# MultiGenPI.net
KiCad netlist of a schematic drawn in Altium Designer
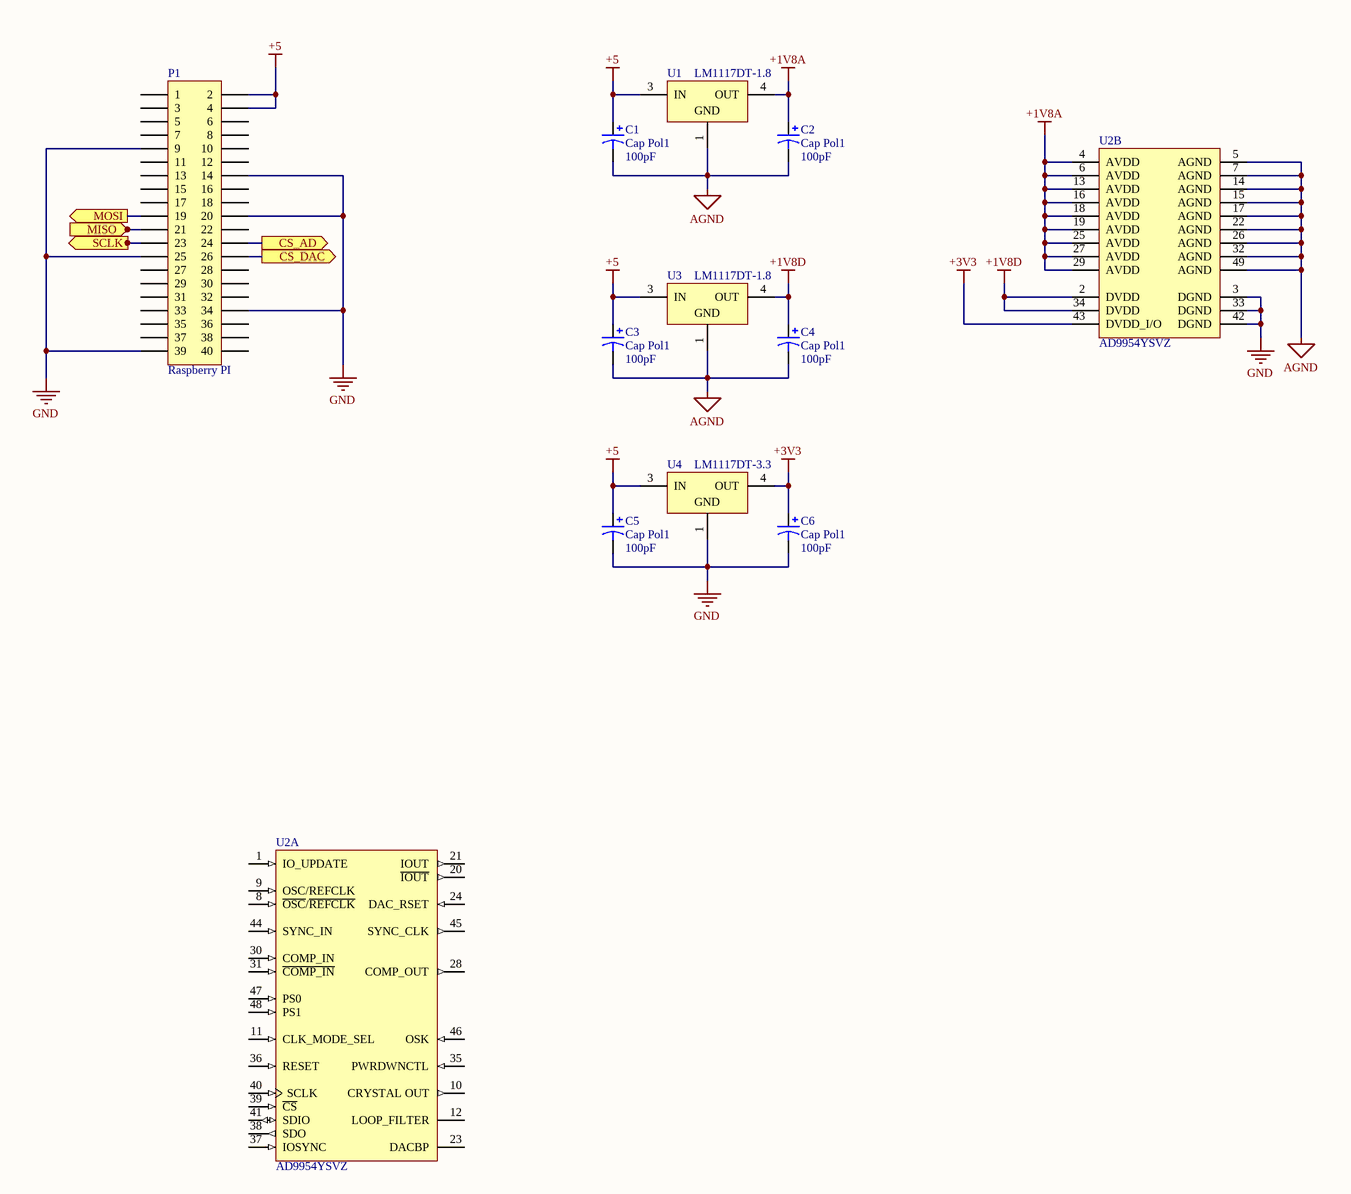
[diagram p0: MultiGenPI.SchDoc]

(export (version "E")
  (design (tool "Eeschema 10.0.6"))
  (components
    (comp (ref "C1")
      (value "Cap Pol1")
      (footprint "RB7.6-15")
      (description "Polarized Capacitor (Radial)")
      (fields (field (name "ALTIUM_VALUE") "100pF") (field (name "PUBLISHER") "Altium Limited"))
      (libsource (lib "Miscellaneous Devices") (part "Cap Pol1"))
    )
    (comp (ref "C2")
      (value "Cap Pol1")
      (footprint "RB7.6-15")
      (description "Polarized Capacitor (Radial)")
      (fields (field (name "ALTIUM_VALUE") "100pF") (field (name "PUBLISHER") "Altium Limited"))
      (libsource (lib "Miscellaneous Devices") (part "Cap Pol1"))
    )
    (comp (ref "C3")
      (value "Cap Pol1")
      (footprint "RB7.6-15")
      (description "Polarized Capacitor (Radial)")
      (fields (field (name "ALTIUM_VALUE") "100pF") (field (name "PUBLISHER") "Altium Limited"))
      (libsource (lib "Miscellaneous Devices") (part "Cap Pol1"))
    )
    (comp (ref "C4")
      (value "Cap Pol1")
      (footprint "RB7.6-15")
      (description "Polarized Capacitor (Radial)")
      (fields (field (name "ALTIUM_VALUE") "100pF") (field (name "PUBLISHER") "Altium Limited"))
      (libsource (lib "Miscellaneous Devices") (part "Cap Pol1"))
    )
    (comp (ref "C5")
      (value "Cap Pol1")
      (footprint "RB7.6-15")
      (description "Polarized Capacitor (Radial)")
      (fields (field (name "ALTIUM_VALUE") "100pF") (field (name "PUBLISHER") "Altium Limited"))
      (libsource (lib "Miscellaneous Devices") (part "Cap Pol1"))
    )
    (comp (ref "C6")
      (value "Cap Pol1")
      (footprint "RB7.6-15")
      (description "Polarized Capacitor (Radial)")
      (fields (field (name "ALTIUM_VALUE") "100pF") (field (name "PUBLISHER") "Altium Limited"))
      (libsource (lib "Miscellaneous Devices") (part "Cap Pol1"))
    )
    (comp (ref "P1")
      (value "Raspberry PI")
      (footprint "HDR2X20")
      (description "Header, 20-Pin, Dual row")
      (fields (field (name "PUBLISHER") "Altium Limited"))
      (libsource (lib "Miscellaneous Connectors") (part "Header 20X2"))
    )
    (comp (ref "U1")
      (value "LM1117DT-1.8")
      (footprint "TD03B_N")
      (description "800mA Low-Dropout Linear Regulator, 3-pin TO-252")
      (fields (field (name "MANUFACTURER") "National Semiconductor"))
      (libsource (lib "National Semiconductor LDO") (part "LM1117DT-1.8"))
    )
    (comp (ref "U2")
      (value "AD9954YSVZ")
      (footprint "ADI-SV-48-4_N")
      (description "400 MSPS, 14-Bit, 1.8 V CMOS Direct Digital Synthesizer, Serial, SV-48-4, 250 Tray, Pb-Free")
      (libsource (lib "Analog Devices RF IF Direct Digital Synthesis") (part "AD9954YSVZ"))
    )
    (comp (ref "U3")
      (value "LM1117DT-1.8")
      (footprint "TD03B_N")
      (description "800mA Low-Dropout Linear Regulator, 3-pin TO-252")
      (fields (field (name "MANUFACTURER") "National Semiconductor"))
      (libsource (lib "National Semiconductor LDO") (part "LM1117DT-1.8"))
    )
    (comp (ref "U4")
      (value "LM1117DT-3.3")
      (footprint "TD03B_N")
      (description "800mA Low-Dropout Linear Regulator, 3-pin TO-252")
      (fields (field (name "MANUFACTURER") "National Semiconductor"))
      (libsource (lib "National Semiconductor LDO") (part "LM1117DT-3.3"))
    )
  )
  (nets
    (net (code "1") (name "+1V8A") (class "Default")
      (node (ref "C2") (pin "1") (pinfunction "1_1") (pintype "passive"))
      (node (ref "U1") (pin "4") (pinfunction "OUT_4") (pintype "power_in"))
      (node (ref "U2") (pin "13") (pinfunction "AVDD_13") (pintype "power_in"))
      (node (ref "U2") (pin "16") (pinfunction "AVDD_16") (pintype "power_in"))
      (node (ref "U2") (pin "18") (pinfunction "AVDD_18") (pintype "power_in"))
      (node (ref "U2") (pin "19") (pinfunction "AVDD_19") (pintype "power_in"))
      (node (ref "U2") (pin "25") (pinfunction "AVDD_25") (pintype "power_in"))
      (node (ref "U2") (pin "27") (pinfunction "AVDD_27") (pintype "power_in"))
      (node (ref "U2") (pin "29") (pinfunction "AVDD_29") (pintype "power_in"))
      (node (ref "U2") (pin "4") (pinfunction "AVDD_4") (pintype "power_in"))
      (node (ref "U2") (pin "6") (pinfunction "AVDD_6") (pintype "power_in"))
    )
    (net (code "2") (name "+1V8D") (class "Default")
      (node (ref "C4") (pin "1") (pinfunction "1_1") (pintype "passive"))
      (node (ref "U2") (pin "2") (pinfunction "DVDD_2") (pintype "power_in"))
      (node (ref "U2") (pin "34") (pinfunction "DVDD_34") (pintype "power_in"))
      (node (ref "U3") (pin "4") (pinfunction "OUT_4") (pintype "power_in"))
    )
    (net (code "3") (name "+3V3") (class "Default")
      (node (ref "C6") (pin "1") (pinfunction "1_1") (pintype "passive"))
      (node (ref "U2") (pin "43") (pinfunction "DVDD_I/O_43") (pintype "power_in"))
      (node (ref "U4") (pin "4") (pinfunction "OUT_4") (pintype "power_in"))
    )
    (net (code "4") (name "+5") (class "Default")
      (node (ref "C1") (pin "1") (pinfunction "1_1") (pintype "passive"))
      (node (ref "C3") (pin "1") (pinfunction "1_1") (pintype "passive"))
      (node (ref "C5") (pin "1") (pinfunction "1_1") (pintype "passive"))
      (node (ref "P1") (pin "2") (pinfunction "2_2") (pintype "passive"))
      (node (ref "P1") (pin "4") (pinfunction "4_4") (pintype "passive"))
      (node (ref "U1") (pin "3") (pinfunction "IN_3") (pintype "power_in"))
      (node (ref "U3") (pin "3") (pinfunction "IN_3") (pintype "power_in"))
      (node (ref "U4") (pin "3") (pinfunction "IN_3") (pintype "power_in"))
    )
    (net (code "5") (name "/CS_AD") (class "Default")
      (node (ref "P1") (pin "24") (pinfunction "24_24") (pintype "passive"))
    )
    (net (code "6") (name "/CS_DAC") (class "Default")
      (node (ref "P1") (pin "26") (pinfunction "26_26") (pintype "passive"))
    )
    (net (code "7") (name "/MISO") (class "Default")
      (node (ref "P1") (pin "21") (pinfunction "21_21") (pintype "passive"))
    )
    (net (code "8") (name "/MOSI") (class "Default")
      (node (ref "P1") (pin "19") (pinfunction "19_19") (pintype "passive"))
    )
    (net (code "9") (name "/SCLK") (class "Default")
      (node (ref "P1") (pin "23") (pinfunction "23_23") (pintype "passive"))
    )
    (net (code "10") (name "AGND") (class "Default")
      (node (ref "C1") (pin "2") (pinfunction "2_2") (pintype "passive"))
      (node (ref "C2") (pin "2") (pinfunction "2_2") (pintype "passive"))
      (node (ref "C3") (pin "2") (pinfunction "2_2") (pintype "passive"))
      (node (ref "C4") (pin "2") (pinfunction "2_2") (pintype "passive"))
      (node (ref "U1") (pin "1") (pinfunction "GND_1") (pintype "power_in"))
      (node (ref "U2") (pin "14") (pinfunction "AGND_14") (pintype "power_in"))
      (node (ref "U2") (pin "15") (pinfunction "AGND_15") (pintype "power_in"))
      (node (ref "U2") (pin "17") (pinfunction "AGND_17") (pintype "power_in"))
      (node (ref "U2") (pin "22") (pinfunction "AGND_22") (pintype "power_in"))
      (node (ref "U2") (pin "26") (pinfunction "AGND_26") (pintype "power_in"))
      (node (ref "U2") (pin "32") (pinfunction "AGND_32") (pintype "power_in"))
      (node (ref "U2") (pin "49") (pinfunction "AGND_49") (pintype "power_in"))
      (node (ref "U2") (pin "5") (pinfunction "AGND_5") (pintype "power_in"))
      (node (ref "U2") (pin "7") (pinfunction "AGND_7") (pintype "power_in"))
      (node (ref "U3") (pin "1") (pinfunction "GND_1") (pintype "power_in"))
    )
    (net (code "11") (name "GND") (class "Default")
      (node (ref "C5") (pin "2") (pinfunction "2_2") (pintype "passive"))
      (node (ref "C6") (pin "2") (pinfunction "2_2") (pintype "passive"))
      (node (ref "P1") (pin "14") (pinfunction "14_14") (pintype "passive"))
      (node (ref "P1") (pin "20") (pinfunction "20_20") (pintype "passive"))
      (node (ref "P1") (pin "25") (pinfunction "25_25") (pintype "passive"))
      (node (ref "P1") (pin "34") (pinfunction "34_34") (pintype "passive"))
      (node (ref "P1") (pin "39") (pinfunction "39_39") (pintype "passive"))
      (node (ref "P1") (pin "9") (pinfunction "9_9") (pintype "passive"))
      (node (ref "U2") (pin "3") (pinfunction "DGND_3") (pintype "power_in"))
      (node (ref "U2") (pin "33") (pinfunction "DGND_33") (pintype "power_in"))
      (node (ref "U2") (pin "42") (pinfunction "DGND_42") (pintype "power_in"))
      (node (ref "U4") (pin "1") (pinfunction "GND_1") (pintype "power_in"))
    )
    (net (code "12") (name "unconnected-(P1-Pad1)") (class "Default")
      (node (ref "P1") (pin "1") (pinfunction "1_1") (pintype "passive"))
    )
    (net (code "13") (name "unconnected-(P1-Pad3)") (class "Default")
      (node (ref "P1") (pin "3") (pinfunction "3_3") (pintype "passive"))
    )
    (net (code "14") (name "unconnected-(P1-Pad5)") (class "Default")
      (node (ref "P1") (pin "5") (pinfunction "5_5") (pintype "passive"))
    )
    (net (code "15") (name "unconnected-(P1-Pad6)") (class "Default")
      (node (ref "P1") (pin "6") (pinfunction "6_6") (pintype "passive"))
    )
    (net (code "16") (name "unconnected-(P1-Pad7)") (class "Default")
      (node (ref "P1") (pin "7") (pinfunction "7_7") (pintype "passive"))
    )
    (net (code "17") (name "unconnected-(P1-Pad8)") (class "Default")
      (node (ref "P1") (pin "8") (pinfunction "8_8") (pintype "passive"))
    )
    (net (code "18") (name "unconnected-(P1-Pad10)") (class "Default")
      (node (ref "P1") (pin "10") (pinfunction "10_10") (pintype "passive"))
    )
    (net (code "19") (name "unconnected-(P1-Pad11)") (class "Default")
      (node (ref "P1") (pin "11") (pinfunction "11_11") (pintype "passive"))
    )
    (net (code "20") (name "unconnected-(P1-Pad12)") (class "Default")
      (node (ref "P1") (pin "12") (pinfunction "12_12") (pintype "passive"))
    )
    (net (code "21") (name "unconnected-(P1-Pad13)") (class "Default")
      (node (ref "P1") (pin "13") (pinfunction "13_13") (pintype "passive"))
    )
    (net (code "22") (name "unconnected-(P1-Pad15)") (class "Default")
      (node (ref "P1") (pin "15") (pinfunction "15_15") (pintype "passive"))
    )
    (net (code "23") (name "unconnected-(P1-Pad16)") (class "Default")
      (node (ref "P1") (pin "16") (pinfunction "16_16") (pintype "passive"))
    )
    (net (code "24") (name "unconnected-(P1-Pad17)") (class "Default")
      (node (ref "P1") (pin "17") (pinfunction "17_17") (pintype "passive"))
    )
    (net (code "25") (name "unconnected-(P1-Pad18)") (class "Default")
      (node (ref "P1") (pin "18") (pinfunction "18_18") (pintype "passive"))
    )
    (net (code "26") (name "unconnected-(P1-Pad22)") (class "Default")
      (node (ref "P1") (pin "22") (pinfunction "22_22") (pintype "passive"))
    )
    (net (code "27") (name "unconnected-(P1-Pad27)") (class "Default")
      (node (ref "P1") (pin "27") (pinfunction "27_27") (pintype "passive"))
    )
    (net (code "28") (name "unconnected-(P1-Pad28)") (class "Default")
      (node (ref "P1") (pin "28") (pinfunction "28_28") (pintype "passive"))
    )
    (net (code "29") (name "unconnected-(P1-Pad29)") (class "Default")
      (node (ref "P1") (pin "29") (pinfunction "29_29") (pintype "passive"))
    )
    (net (code "30") (name "unconnected-(P1-Pad30)") (class "Default")
      (node (ref "P1") (pin "30") (pinfunction "30_30") (pintype "passive"))
    )
    (net (code "31") (name "unconnected-(P1-Pad31)") (class "Default")
      (node (ref "P1") (pin "31") (pinfunction "31_31") (pintype "passive"))
    )
    (net (code "32") (name "unconnected-(P1-Pad32)") (class "Default")
      (node (ref "P1") (pin "32") (pinfunction "32_32") (pintype "passive"))
    )
    (net (code "33") (name "unconnected-(P1-Pad33)") (class "Default")
      (node (ref "P1") (pin "33") (pinfunction "33_33") (pintype "passive"))
    )
    (net (code "34") (name "unconnected-(P1-Pad35)") (class "Default")
      (node (ref "P1") (pin "35") (pinfunction "35_35") (pintype "passive"))
    )
    (net (code "35") (name "unconnected-(P1-Pad36)") (class "Default")
      (node (ref "P1") (pin "36") (pinfunction "36_36") (pintype "passive"))
    )
    (net (code "36") (name "unconnected-(P1-Pad37)") (class "Default")
      (node (ref "P1") (pin "37") (pinfunction "37_37") (pintype "passive"))
    )
    (net (code "37") (name "unconnected-(P1-Pad38)") (class "Default")
      (node (ref "P1") (pin "38") (pinfunction "38_38") (pintype "passive"))
    )
    (net (code "38") (name "unconnected-(P1-Pad40)") (class "Default")
      (node (ref "P1") (pin "40") (pinfunction "40_40") (pintype "passive"))
    )
    (net (code "39") (name "unconnected-(U2A-CLK_MODE_SEL-Pad11)") (class "Default")
      (node (ref "U2") (pin "11") (pinfunction "CLK_MODE_SEL_11") (pintype "input"))
    )
    (net (code "40") (name "unconnected-(U2A-COMP_IN-Pad30)") (class "Default")
      (node (ref "U2") (pin "30") (pinfunction "COMP_IN_30") (pintype "input"))
    )
    (net (code "41") (name "unconnected-(U2A-COMP_OUT-Pad28)") (class "Default")
      (node (ref "U2") (pin "28") (pinfunction "COMP_OUT_28") (pintype "output"))
    )
    (net (code "42") (name "unconnected-(U2A-CRYSTAL_OUT-Pad10)") (class "Default")
      (node (ref "U2") (pin "10") (pinfunction "CRYSTAL_OUT_10") (pintype "output"))
    )
    (net (code "43") (name "unconnected-(U2A-DACBP-Pad23)") (class "Default")
      (node (ref "U2") (pin "23") (pinfunction "DACBP_23") (pintype "passive"))
    )
    (net (code "44") (name "unconnected-(U2A-DAC_RSET-Pad24)") (class "Default")
      (node (ref "U2") (pin "24") (pinfunction "DAC_RSET_24") (pintype "input"))
    )
    (net (code "45") (name "unconnected-(U2A-IOSYNC-Pad37)") (class "Default")
      (node (ref "U2") (pin "37") (pinfunction "IOSYNC_37") (pintype "input"))
    )
    (net (code "46") (name "unconnected-(U2A-IOUT-Pad21)") (class "Default")
      (node (ref "U2") (pin "21") (pinfunction "IOUT_21") (pintype "output"))
    )
    (net (code "47") (name "unconnected-(U2A-IO_UPDATE-Pad1)") (class "Default")
      (node (ref "U2") (pin "1") (pinfunction "IO_UPDATE_1") (pintype "input"))
    )
    (net (code "48") (name "unconnected-(U2A-LOOP_FILTER-Pad12)") (class "Default")
      (node (ref "U2") (pin "12") (pinfunction "LOOP_FILTER_12") (pintype "passive"))
    )
    (net (code "49") (name "unconnected-(U2A-OSC{slash}REFCLK-Pad9)") (class "Default")
      (node (ref "U2") (pin "9") (pinfunction "OSC/REFCLK_9") (pintype "input"))
    )
    (net (code "50") (name "unconnected-(U2A-OSK-Pad46)") (class "Default")
      (node (ref "U2") (pin "46") (pinfunction "OSK_46") (pintype "input"))
    )
    (net (code "51") (name "unconnected-(U2A-PS0-Pad47)") (class "Default")
      (node (ref "U2") (pin "47") (pinfunction "PS0_47") (pintype "input"))
    )
    (net (code "52") (name "unconnected-(U2A-PS1-Pad48)") (class "Default")
      (node (ref "U2") (pin "48") (pinfunction "PS1_48") (pintype "input"))
    )
    (net (code "53") (name "unconnected-(U2A-PWRDWNCTL-Pad35)") (class "Default")
      (node (ref "U2") (pin "35") (pinfunction "PWRDWNCTL_35") (pintype "input"))
    )
    (net (code "54") (name "unconnected-(U2A-RESET-Pad36)") (class "Default")
      (node (ref "U2") (pin "36") (pinfunction "RESET_36") (pintype "input"))
    )
    (net (code "55") (name "unconnected-(U2A-SCLK-Pad40)") (class "Default")
      (node (ref "U2") (pin "40") (pinfunction "SCLK_40") (pintype "input"))
    )
    (net (code "56") (name "unconnected-(U2A-SDIO-Pad41)") (class "Default")
      (node (ref "U2") (pin "41") (pinfunction "SDIO_41") (pintype "bidirectional"))
    )
    (net (code "57") (name "unconnected-(U2A-SDO-Pad38)") (class "Default")
      (node (ref "U2") (pin "38") (pinfunction "SDO_38") (pintype "output"))
    )
    (net (code "58") (name "unconnected-(U2A-SYNC_CLK-Pad45)") (class "Default")
      (node (ref "U2") (pin "45") (pinfunction "SYNC_CLK_45") (pintype "output"))
    )
    (net (code "59") (name "unconnected-(U2A-SYNC_IN-Pad44)") (class "Default")
      (node (ref "U2") (pin "44") (pinfunction "SYNC_IN_44") (pintype "input"))
    )
    (net (code "60") (name "unconnected-(U2A-~{COMP_IN}-Pad31)") (class "Default")
      (node (ref "U2") (pin "31") (pinfunction "~{COMP_IN}_31") (pintype "input"))
    )
    (net (code "61") (name "unconnected-(U2A-~{CS}-Pad39)") (class "Default")
      (node (ref "U2") (pin "39") (pinfunction "~{CS}_39") (pintype "input"))
    )
    (net (code "62") (name "unconnected-(U2A-~{IOUT}-Pad20)") (class "Default")
      (node (ref "U2") (pin "20") (pinfunction "~{IOUT}_20") (pintype "output"))
    )
    (net (code "63") (name "unconnected-(U2A-~{OSC}{slash}~{REFCLK}-Pad8)") (class "Default")
      (node (ref "U2") (pin "8") (pinfunction "~{OSC}/~{REFCLK}_8") (pintype "input"))
    )
  )
)
